# QSPI_WSON.net
KiCad netlist of a schematic drawn in Altium Designer
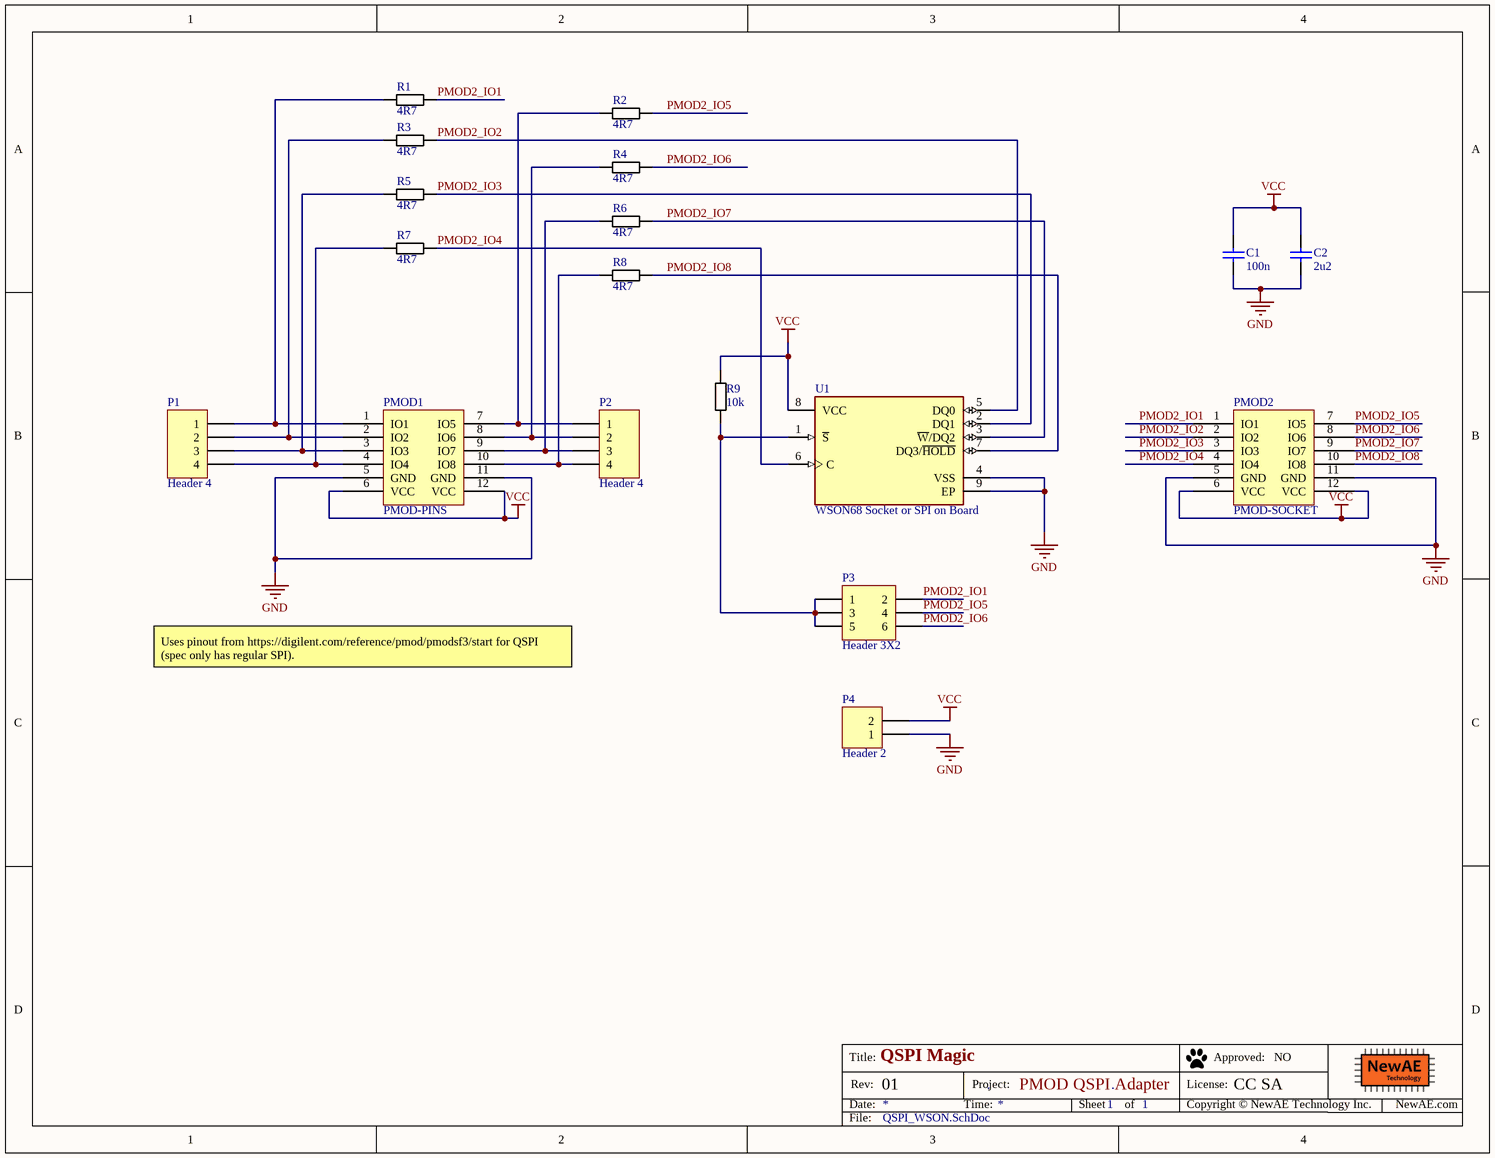
[diagram p0: QSPI_WSON.SchDoc]

(export (version "E")
  (design (tool "Eeschema 10.0.6"))
  (components
    (comp (ref "C1")
      (value "100n")
      (footprint "CAPC0603_M")
      (description "100n, 0603")
      (fields (field (name "PART NUMBER") "CCHIP-100n-0603"))
      (libsource (lib "NewAE_AltiumLib") (part "CAP"))
    )
    (comp (ref "C2")
      (value "2u2")
      (footprint "CAPC0603_M")
      (description "2u2, 0603")
      (fields (field (name "PART NUMBER") "CCHIP-2u2-0603"))
      (libsource (lib "NewAE_AltiumLib") (part "CAP"))
    )
    (comp (ref "P1")
      (value "Header 4")
      (footprint "HDR1X4")
      (description "Header, 4-Pin")
      (fields (field (name "PUBLISHER") "Altium Limited"))
      (libsource (lib "") (part "Header 4_1"))
    )
    (comp (ref "P2")
      (value "Header 4")
      (footprint "HDR1X4")
      (description "Header, 4-Pin")
      (fields (field (name "PUBLISHER") "Altium Limited"))
      (libsource (lib "Miscellaneous Connectors") (part "Header 4"))
    )
    (comp (ref "P3")
      (value "Header 3X2")
      (footprint "HDR2X3")
      (description "Header, 3-Pin, Dual row")
      (fields (field (name "PUBLISHER") "Altium Limited"))
      (libsource (lib "NewAE Technology") (part "Header 3X2H"))
    )
    (comp (ref "P4")
      (value "Header 2")
      (footprint "HDR1X2")
      (description "Header, 2-Pin")
      (fields
        (field (name "SOURCE") "CW313_20pinToTarget.SCHLIB")
        (field (name "PUBLISHER") "Altium Limited")
      )
      (libsource (lib "NewAE Technology") (part "Header 2"))
    )
    (comp (ref "PMOD1")
      (value "PMOD-PINS")
      (footprint "PMOD-68021-212HLF-MALE")
      (fields (field (name "PART NUMBER") "PMOD_2ROW_MALERATH"))
      (libsource (lib "NewAE_AltiumLib") (part "12PIN_RA_FEMALE"))
    )
    (comp (ref "PMOD2")
      (value "PMOD-SOCKET")
      (footprint "SAMTEC_SSW_106_02_X_D_RA_PMOD")
      (fields (field (name "PART NUMBER") "PMOD_2ROW_FEMALERATH"))
      (libsource (lib "NewAE_AltiumLib") (part "12PIN_RA_FEMALE"))
    )
    (comp (ref "R1")
      (value "4R7")
      (footprint "RESC1608X55N")
      (description "4R7 res, 0603, 1%, 1/10W")
      (fields (field (name "PART NUMBER") "RCHIP-4R7-0603") (field (name "TOLERANCE") "1%"))
      (libsource (lib "NewAE_AltiumLib") (part "RES-EU"))
    )
    (comp (ref "R2")
      (value "4R7")
      (footprint "RESC1608X55N")
      (description "4R7 res, 0603, 1%, 1/10W")
      (fields (field (name "PART NUMBER") "RCHIP-4R7-0603") (field (name "TOLERANCE") "1%"))
      (libsource (lib "NewAE_AltiumLib") (part "RES-EU"))
    )
    (comp (ref "R3")
      (value "4R7")
      (footprint "RESC1608X55N")
      (description "4R7 res, 0603, 1%, 1/10W")
      (fields (field (name "PART NUMBER") "RCHIP-4R7-0603") (field (name "TOLERANCE") "1%"))
      (libsource (lib "NewAE_AltiumLib") (part "RES-EU"))
    )
    (comp (ref "R4")
      (value "4R7")
      (footprint "RESC1608X55N")
      (description "4R7 res, 0603, 1%, 1/10W")
      (fields (field (name "PART NUMBER") "RCHIP-4R7-0603") (field (name "TOLERANCE") "1%"))
      (libsource (lib "NewAE_AltiumLib") (part "RES-EU"))
    )
    (comp (ref "R5")
      (value "4R7")
      (footprint "RESC1608X55N")
      (description "4R7 res, 0603, 1%, 1/10W")
      (fields (field (name "PART NUMBER") "RCHIP-4R7-0603") (field (name "TOLERANCE") "1%"))
      (libsource (lib "NewAE_AltiumLib") (part "RES-EU"))
    )
    (comp (ref "R6")
      (value "4R7")
      (footprint "RESC1608X55N")
      (description "4R7 res, 0603, 1%, 1/10W")
      (fields (field (name "PART NUMBER") "RCHIP-4R7-0603") (field (name "TOLERANCE") "1%"))
      (libsource (lib "NewAE_AltiumLib") (part "RES-EU"))
    )
    (comp (ref "R7")
      (value "4R7")
      (footprint "RESC1608X55N")
      (description "4R7 res, 0603, 1%, 1/10W")
      (fields (field (name "PART NUMBER") "RCHIP-4R7-0603") (field (name "TOLERANCE") "1%"))
      (libsource (lib "NewAE_AltiumLib") (part "RES-EU"))
    )
    (comp (ref "R8")
      (value "4R7")
      (footprint "RESC1608X55N")
      (description "4R7 res, 0603, 1%, 1/10W")
      (fields (field (name "PART NUMBER") "RCHIP-4R7-0603") (field (name "TOLERANCE") "1%"))
      (libsource (lib "NewAE_AltiumLib") (part "RES-EU"))
    )
    (comp (ref "R9")
      (value "10k")
      (footprint "RESC1608X55N")
      (description "10k res, 0603, 1%, 1/10W")
      (fields (field (name "PART NUMBER") "RCHIP-10K-0603") (field (name "TOLERANCE") "1%"))
      (libsource (lib "") (part "RES-EU_1"))
    )
    (comp (ref "U1")
      (value "WSON68 Socket or SPI on Board")
      (footprint "SOK-SPI-WSON68_ORCHIP")
      (description "WSON-6x8 Socket OR WSON Flash")
      (fields (field (name "PART NUMBER") "SOK-SPI-WSON68_OR_QSPI"))
      (libsource (lib "NewAE_AltiumLib") (part "QSPI_WSON"))
    )
  )
  (nets
    (net (code "1") (name "/PMOD2_IO1") (class "Default")
      (node (ref "P3") (pin "2") (pinfunction "2_2") (pintype "passive"))
      (node (ref "PMOD2") (pin "1") (pinfunction "IO1_1") (pintype "passive"))
      (node (ref "R1") (pin "2") (pinfunction "2_2") (pintype "passive"))
    )
    (net (code "2") (name "/PMOD2_IO2") (class "Default")
      (node (ref "PMOD2") (pin "2") (pinfunction "IO2_2") (pintype "passive"))
      (node (ref "R3") (pin "2") (pinfunction "2_2") (pintype "passive"))
      (node (ref "U1") (pin "5") (pinfunction "DQ0_5") (pintype "bidirectional"))
    )
    (net (code "3") (name "/PMOD2_IO3") (class "Default")
      (node (ref "PMOD2") (pin "3") (pinfunction "IO3_3") (pintype "passive"))
      (node (ref "R5") (pin "2") (pinfunction "2_2") (pintype "passive"))
      (node (ref "U1") (pin "2") (pinfunction "DQ1_2") (pintype "bidirectional"))
    )
    (net (code "4") (name "/PMOD2_IO4") (class "Default")
      (node (ref "PMOD2") (pin "4") (pinfunction "IO4_4") (pintype "passive"))
      (node (ref "R7") (pin "2") (pinfunction "2_2") (pintype "passive"))
      (node (ref "U1") (pin "6") (pinfunction "C_6") (pintype "input"))
    )
    (net (code "5") (name "/PMOD2_IO5") (class "Default")
      (node (ref "P3") (pin "4") (pinfunction "4_4") (pintype "passive"))
      (node (ref "PMOD2") (pin "7") (pinfunction "IO5_7") (pintype "passive"))
      (node (ref "R2") (pin "2") (pinfunction "2_2") (pintype "passive"))
    )
    (net (code "6") (name "/PMOD2_IO6") (class "Default")
      (node (ref "P3") (pin "6") (pinfunction "6_6") (pintype "passive"))
      (node (ref "PMOD2") (pin "8") (pinfunction "IO6_8") (pintype "passive"))
      (node (ref "R4") (pin "2") (pinfunction "2_2") (pintype "passive"))
    )
    (net (code "7") (name "/PMOD2_IO7") (class "Default")
      (node (ref "PMOD2") (pin "9") (pinfunction "IO7_9") (pintype "passive"))
      (node (ref "R6") (pin "2") (pinfunction "2_2") (pintype "passive"))
      (node (ref "U1") (pin "3") (pinfunction "~{W}/DQ2_3") (pintype "bidirectional"))
    )
    (net (code "8") (name "/PMOD2_IO8") (class "Default")
      (node (ref "PMOD2") (pin "10") (pinfunction "IO8_10") (pintype "passive"))
      (node (ref "R8") (pin "2") (pinfunction "2_2") (pintype "passive"))
      (node (ref "U1") (pin "7") (pinfunction "DQ3/~{HOLD}_7") (pintype "bidirectional"))
    )
    (net (code "9") (name "GND") (class "Default")
      (node (ref "C1") (pin "2") (pinfunction "2_2") (pintype "passive"))
      (node (ref "C2") (pin "2") (pinfunction "2_2") (pintype "passive"))
      (node (ref "P4") (pin "1") (pinfunction "1_1") (pintype "passive"))
      (node (ref "PMOD1") (pin "11") (pinfunction "GND_11") (pintype "passive"))
      (node (ref "PMOD1") (pin "5") (pinfunction "GND_5") (pintype "passive"))
      (node (ref "PMOD2") (pin "11") (pinfunction "GND_11") (pintype "passive"))
      (node (ref "PMOD2") (pin "5") (pinfunction "GND_5") (pintype "passive"))
      (node (ref "U1") (pin "4") (pinfunction "VSS_4") (pintype "power_in"))
      (node (ref "U1") (pin "9") (pinfunction "EP_9") (pintype "power_in"))
    )
    (net (code "10") (name "Net-(PMOD1-IO1)") (class "Default")
      (node (ref "P1") (pin "1") (pinfunction "1_1") (pintype "passive"))
      (node (ref "PMOD1") (pin "1") (pinfunction "IO1_1") (pintype "passive"))
      (node (ref "R1") (pin "1") (pinfunction "1_1") (pintype "passive"))
    )
    (net (code "11") (name "Net-(PMOD1-IO2)") (class "Default")
      (node (ref "P1") (pin "2") (pinfunction "2_2") (pintype "passive"))
      (node (ref "PMOD1") (pin "2") (pinfunction "IO2_2") (pintype "passive"))
      (node (ref "R3") (pin "1") (pinfunction "1_1") (pintype "passive"))
    )
    (net (code "12") (name "Net-(PMOD1-IO3)") (class "Default")
      (node (ref "P1") (pin "3") (pinfunction "3_3") (pintype "passive"))
      (node (ref "PMOD1") (pin "3") (pinfunction "IO3_3") (pintype "passive"))
      (node (ref "R5") (pin "1") (pinfunction "1_1") (pintype "passive"))
    )
    (net (code "13") (name "Net-(PMOD1-IO4)") (class "Default")
      (node (ref "P1") (pin "4") (pinfunction "4_4") (pintype "passive"))
      (node (ref "PMOD1") (pin "4") (pinfunction "IO4_4") (pintype "passive"))
      (node (ref "R7") (pin "1") (pinfunction "1_1") (pintype "passive"))
    )
    (net (code "14") (name "Net-(PMOD1-IO5)") (class "Default")
      (node (ref "P2") (pin "1") (pinfunction "1_1") (pintype "passive"))
      (node (ref "PMOD1") (pin "7") (pinfunction "IO5_7") (pintype "passive"))
      (node (ref "R2") (pin "1") (pinfunction "1_1") (pintype "passive"))
    )
    (net (code "15") (name "Net-(PMOD1-IO6)") (class "Default")
      (node (ref "P2") (pin "2") (pinfunction "2_2") (pintype "passive"))
      (node (ref "PMOD1") (pin "8") (pinfunction "IO6_8") (pintype "passive"))
      (node (ref "R4") (pin "1") (pinfunction "1_1") (pintype "passive"))
    )
    (net (code "16") (name "Net-(PMOD1-IO7)") (class "Default")
      (node (ref "P2") (pin "3") (pinfunction "3_3") (pintype "passive"))
      (node (ref "PMOD1") (pin "9") (pinfunction "IO7_9") (pintype "passive"))
      (node (ref "R6") (pin "1") (pinfunction "1_1") (pintype "passive"))
    )
    (net (code "17") (name "Net-(PMOD1-IO8)") (class "Default")
      (node (ref "P2") (pin "4") (pinfunction "4_4") (pintype "passive"))
      (node (ref "PMOD1") (pin "10") (pinfunction "IO8_10") (pintype "passive"))
      (node (ref "R8") (pin "1") (pinfunction "1_1") (pintype "passive"))
    )
    (net (code "18") (name "Net-(U1-~{S})") (class "Default")
      (node (ref "P3") (pin "1") (pinfunction "1_1") (pintype "passive"))
      (node (ref "P3") (pin "3") (pinfunction "3_3") (pintype "passive"))
      (node (ref "P3") (pin "5") (pinfunction "5_5") (pintype "passive"))
      (node (ref "R9") (pin "1") (pinfunction "1_1") (pintype "passive"))
      (node (ref "U1") (pin "1") (pinfunction "~{S}_1") (pintype "input"))
    )
    (net (code "19") (name "VCC") (class "Default")
      (node (ref "C1") (pin "1") (pinfunction "1_1") (pintype "passive"))
      (node (ref "C2") (pin "1") (pinfunction "1_1") (pintype "passive"))
      (node (ref "P4") (pin "2") (pinfunction "2_2") (pintype "passive"))
      (node (ref "PMOD1") (pin "12") (pinfunction "VCC_12") (pintype "passive"))
      (node (ref "PMOD1") (pin "6") (pinfunction "VCC_6") (pintype "passive"))
      (node (ref "PMOD2") (pin "12") (pinfunction "VCC_12") (pintype "passive"))
      (node (ref "PMOD2") (pin "6") (pinfunction "VCC_6") (pintype "passive"))
      (node (ref "R9") (pin "2") (pinfunction "2_2") (pintype "passive"))
      (node (ref "U1") (pin "8") (pinfunction "VCC_8") (pintype "power_in"))
    )
  )
)
